# DK_STM32L151.net
KiCad netlist of a schematic drawn in Altium Designer
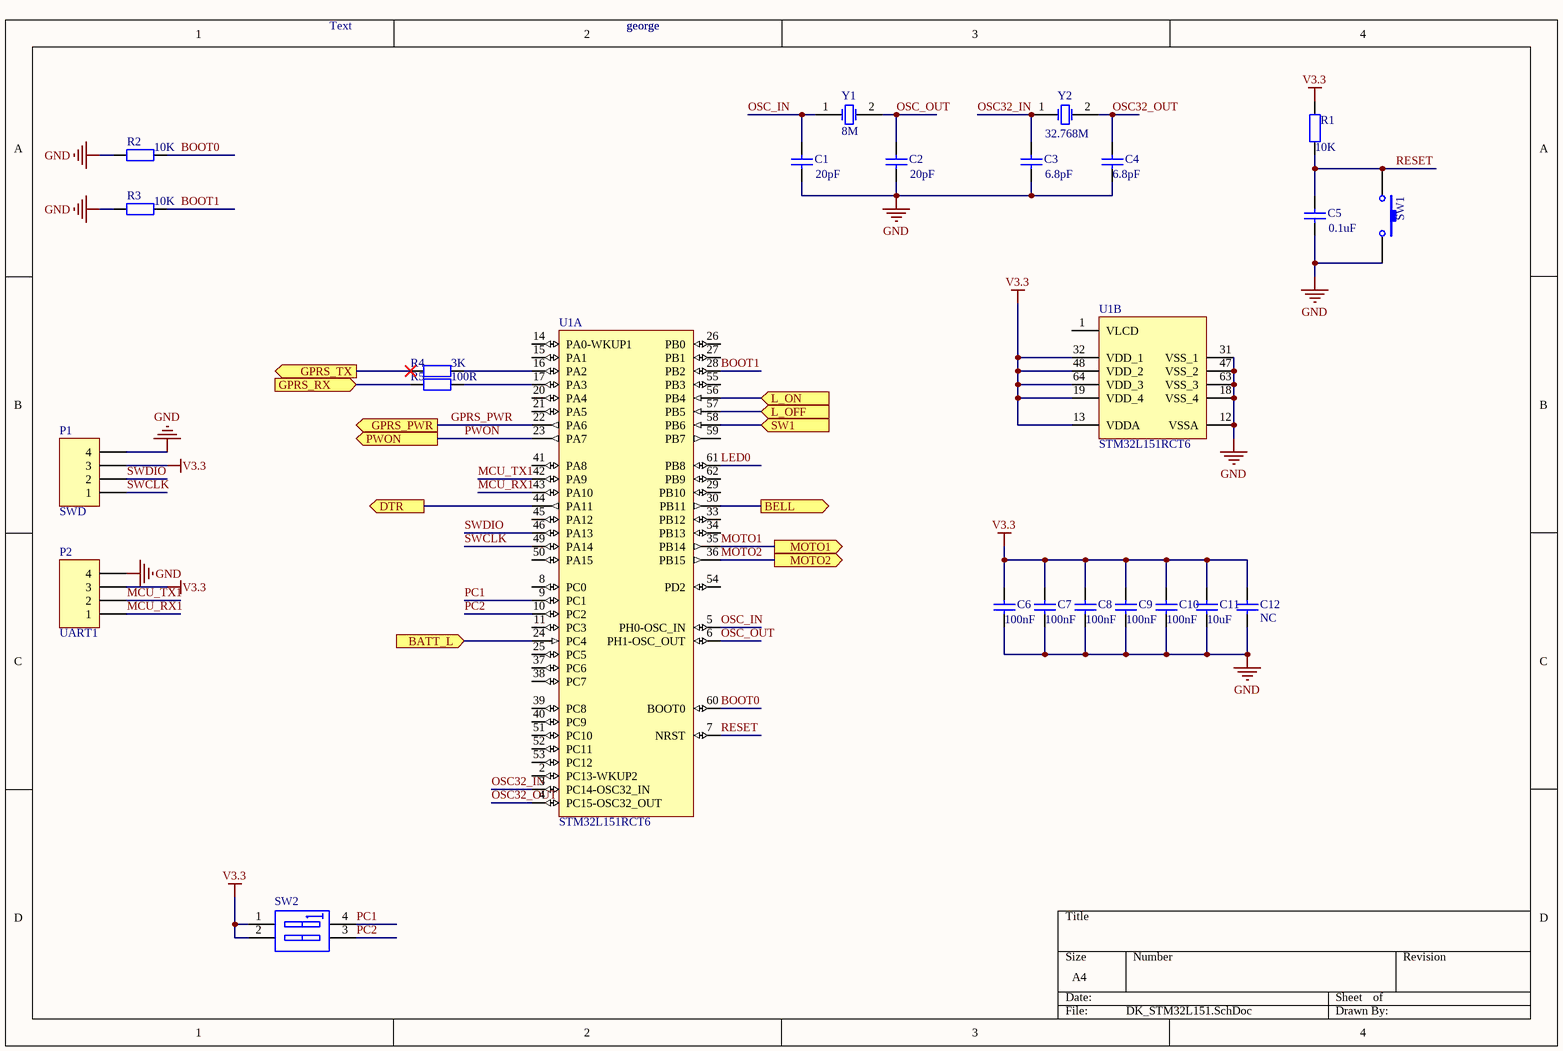
[diagram p0: DK_STM32L151.SchDoc]

(export (version "E")
  (design (tool "Eeschema 10.0.6"))
  (components
    (comp (ref "C1")
      (value "20pF")
      (footprint "0603")
      (description "Capacitor")
      (fields (field (name "Comment") "Cap") (field (name "PUBLISHER") "Altium Limited"))
      (libsource (lib "Miscellaneous Devices") (part "Cap"))
    )
    (comp (ref "C2")
      (value "20pF")
      (footprint "0603")
      (description "Capacitor")
      (fields (field (name "Comment") "Cap") (field (name "PUBLISHER") "Altium Limited"))
      (libsource (lib "Miscellaneous Devices") (part "Cap"))
    )
    (comp (ref "C3")
      (value "6.8pF")
      (footprint "0603")
      (description "Capacitor")
      (fields (field (name "Comment") "Cap") (field (name "PUBLISHER") "Altium Limited"))
      (libsource (lib "Miscellaneous Devices") (part "Cap"))
    )
    (comp (ref "C4")
      (value "6.8pF")
      (footprint "0603")
      (description "Capacitor")
      (fields (field (name "Comment") "Cap") (field (name "PUBLISHER") "Altium Limited"))
      (libsource (lib "Miscellaneous Devices") (part "Cap"))
    )
    (comp (ref "C5")
      (value "0.1uF")
      (footprint "0603")
      (description "Capacitor")
      (fields (field (name "Comment") "Cap") (field (name "PUBLISHER") "Altium Limited"))
      (libsource (lib "Miscellaneous Devices") (part "Cap"))
    )
    (comp (ref "C6")
      (value "100nF")
      (footprint "0603")
      (description "Capacitor")
      (fields (field (name "Comment") "Cap") (field (name "PUBLISHER") "Altium Limited"))
      (libsource (lib "Miscellaneous Devices") (part "Cap"))
    )
    (comp (ref "C7")
      (value "100nF")
      (footprint "0603")
      (description "Capacitor")
      (fields (field (name "Comment") "Cap") (field (name "PUBLISHER") "Altium Limited"))
      (libsource (lib "Miscellaneous Devices") (part "Cap"))
    )
    (comp (ref "C8")
      (value "100nF")
      (footprint "0603")
      (description "Capacitor")
      (fields (field (name "Comment") "Cap") (field (name "PUBLISHER") "Altium Limited"))
      (libsource (lib "Miscellaneous Devices") (part "Cap"))
    )
    (comp (ref "C9")
      (value "100nF")
      (footprint "0603")
      (description "Capacitor")
      (fields (field (name "Comment") "Cap") (field (name "PUBLISHER") "Altium Limited"))
      (libsource (lib "Miscellaneous Devices") (part "Cap"))
    )
    (comp (ref "C10")
      (value "100nF")
      (footprint "0603")
      (description "Capacitor")
      (fields (field (name "Comment") "Cap") (field (name "PUBLISHER") "Altium Limited"))
      (libsource (lib "Miscellaneous Devices") (part "Cap"))
    )
    (comp (ref "C11")
      (value "10uF")
      (footprint "0603")
      (description "Capacitor")
      (fields (field (name "Comment") "Cap") (field (name "PUBLISHER") "Altium Limited"))
      (libsource (lib "Miscellaneous Devices") (part "Cap"))
    )
    (comp (ref "C12")
      (value "NC")
      (footprint "0603")
      (description "Capacitor")
      (fields (field (name "PUBLISHER") "Altium Limited"))
      (libsource (lib "Miscellaneous Devices") (part "Cap"))
    )
    (comp (ref "P1")
      (value "SWD")
      (footprint "HDR1X4")
      (description "Header, 4-Pin")
      (fields (field (name "PUBLISHER") "Altium Limited"))
      (libsource (lib "Miscellaneous Connectors") (part "Header 4"))
    )
    (comp (ref "P2")
      (value "UART1")
      (footprint "HDR1X4")
      (description "Header, 4-Pin")
      (fields (field (name "PUBLISHER") "Altium Limited"))
      (libsource (lib "Miscellaneous Connectors") (part "Header 4"))
    )
    (comp (ref "R1")
      (value "10K")
      (footprint "0603")
      (description "Resistor")
      (fields (field (name "Comment") "Res2") (field (name "PUBLISHER") "Altium Limited"))
      (libsource (lib "") (part "Res2_1"))
    )
    (comp (ref "R2")
      (value "10K")
      (footprint "0603")
      (description "Resistor")
      (fields (field (name "Comment") "Res2") (field (name "PUBLISHER") "Altium Limited"))
      (libsource (lib "Miscellaneous Devices") (part "Res2"))
    )
    (comp (ref "R3")
      (value "10K")
      (footprint "0603")
      (description "Resistor")
      (fields (field (name "Comment") "Res2") (field (name "PUBLISHER") "Altium Limited"))
      (libsource (lib "Miscellaneous Devices") (part "Res2"))
    )
    (comp (ref "R4")
      (value "3K")
      (footprint "0603")
      (description "Resistor")
      (fields (field (name "Comment") "Res2") (field (name "PUBLISHER") "Altium Limited"))
      (libsource (lib "Miscellaneous Devices") (part "Res2"))
    )
    (comp (ref "R5")
      (value "100R")
      (footprint "0603")
      (description "Resistor")
      (fields (field (name "Comment") "Res2") (field (name "PUBLISHER") "Altium Limited"))
      (libsource (lib "Miscellaneous Devices") (part "Res2"))
    )
    (comp (ref "SW1")
      (value "SW-PB")
      (footprint "3*6*4.3")
      (description "Switch")
      (fields (field (name "PUBLISHER") "Altium Limited"))
      (libsource (lib "Miscellaneous Devices") (part "SW-PB"))
    )
    (comp (ref "SW2")
      (value "SW DIP-2")
      (footprint "SW-2*4")
      (description "DIP Switch, 2 Position, SPST")
      (fields (field (name "PUBLISHER") "Altium Limited"))
      (libsource (lib "Miscellaneous Devices") (part "SW DIP-2"))
    )
    (comp (ref "U1")
      (value "STM32L151RCT6")
      (footprint "LQFP64")
      (fields (field (name "MANUFACTURER") "STMicroelectronics"))
      (libsource (lib "STMicroelectronics STM32 L1") (part "STM32L151RCT6"))
    )
    (comp (ref "Y1")
      (value "8M")
      (footprint "SMT-OSC")
      (description "Crystal Oscillator")
      (fields (field (name "PUBLISHER") "Altium Limited"))
      (libsource (lib "Miscellaneous Devices") (part "XTAL"))
    )
    (comp (ref "Y2")
      (value "32.768M")
      (footprint "XTAL32.786")
      (description "Crystal Oscillator")
      (fields (field (name "PUBLISHER") "Altium Limited"))
      (libsource (lib "Miscellaneous Devices") (part "XTAL"))
    )
  )
  (nets
    (net (code "1") (name "/BATT_L") (class "Default")
      (node (ref "U1") (pin "24") (pinfunction "PC4_24") (pintype "input"))
    )
    (net (code "2") (name "/BELL") (class "Default")
      (node (ref "U1") (pin "30") (pinfunction "PB11_30") (pintype "output"))
    )
    (net (code "3") (name "/BOOT0") (class "Default")
      (node (ref "R2") (pin "2") (pinfunction "2_2") (pintype "passive"))
      (node (ref "U1") (pin "60") (pinfunction "BOOT0_60") (pintype "bidirectional"))
    )
    (net (code "4") (name "/BOOT1") (class "Default")
      (node (ref "R3") (pin "2") (pinfunction "2_2") (pintype "passive"))
      (node (ref "U1") (pin "28") (pinfunction "PB2_28") (pintype "bidirectional"))
    )
    (net (code "5") (name "/DTR") (class "Default")
      (node (ref "U1") (pin "44") (pinfunction "PA11_44") (pintype "output"))
    )
    (net (code "6") (name "/GPRS_PWR") (class "Default")
      (node (ref "U1") (pin "22") (pinfunction "PA6_22") (pintype "output"))
    )
    (net (code "7") (name "/GPRS_RX") (class "Default")
      (node (ref "R5") (pin "1") (pinfunction "1_1") (pintype "passive"))
    )
    (net (code "8") (name "/GPRS_TX") (class "Default")
      (node (ref "R4") (pin "1") (pinfunction "1_1") (pintype "passive+no_connect"))
    )
    (net (code "9") (name "/LED0") (class "Default")
      (node (ref "U1") (pin "61") (pinfunction "PB8_61") (pintype "bidirectional"))
    )
    (net (code "10") (name "/L_OFF") (class "Default")
      (node (ref "U1") (pin "57") (pinfunction "PB5_57") (pintype "input"))
    )
    (net (code "11") (name "/L_ON") (class "Default")
      (node (ref "U1") (pin "56") (pinfunction "PB4_56") (pintype "input"))
    )
    (net (code "12") (name "/MCU_RX1") (class "Default")
      (node (ref "P2") (pin "1") (pinfunction "1_1") (pintype "passive"))
      (node (ref "U1") (pin "43") (pinfunction "PA10_43") (pintype "bidirectional"))
    )
    (net (code "13") (name "/MCU_TX1") (class "Default")
      (node (ref "P2") (pin "2") (pinfunction "2_2") (pintype "passive"))
      (node (ref "U1") (pin "42") (pinfunction "PA9_42") (pintype "bidirectional"))
    )
    (net (code "14") (name "/MOTO1") (class "Default")
      (node (ref "U1") (pin "35") (pinfunction "PB14_35") (pintype "output"))
    )
    (net (code "15") (name "/MOTO2") (class "Default")
      (node (ref "U1") (pin "36") (pinfunction "PB15_36") (pintype "output"))
    )
    (net (code "16") (name "/OSC32_IN") (class "Default")
      (node (ref "C3") (pin "2") (pinfunction "2_2") (pintype "passive"))
      (node (ref "U1") (pin "3") (pinfunction "PC14-OSC32_IN_3") (pintype "bidirectional"))
      (node (ref "Y2") (pin "1") (pinfunction "OSC1_1") (pintype "passive"))
    )
    (net (code "17") (name "/OSC32_OUT") (class "Default")
      (node (ref "C4") (pin "2") (pinfunction "2_2") (pintype "passive"))
      (node (ref "U1") (pin "4") (pinfunction "PC15-OSC32_OUT_4") (pintype "bidirectional"))
      (node (ref "Y2") (pin "2") (pinfunction "OSC2_2") (pintype "passive"))
    )
    (net (code "18") (name "/OSC_IN") (class "Default")
      (node (ref "C1") (pin "2") (pinfunction "2_2") (pintype "passive"))
      (node (ref "U1") (pin "5") (pinfunction "PH0-OSC_IN_5") (pintype "bidirectional"))
      (node (ref "Y1") (pin "1") (pinfunction "OSC1_1") (pintype "passive"))
    )
    (net (code "19") (name "/OSC_OUT") (class "Default")
      (node (ref "C2") (pin "2") (pinfunction "2_2") (pintype "passive"))
      (node (ref "U1") (pin "6") (pinfunction "PH1-OSC_OUT_6") (pintype "bidirectional"))
      (node (ref "Y1") (pin "2") (pinfunction "OSC2_2") (pintype "passive"))
    )
    (net (code "20") (name "/PC1") (class "Default")
      (node (ref "SW2") (pin "4") (pinfunction "B1_4") (pintype "passive"))
      (node (ref "U1") (pin "9") (pinfunction "PC1_9") (pintype "bidirectional"))
    )
    (net (code "21") (name "/PC2") (class "Default")
      (node (ref "SW2") (pin "3") (pinfunction "B2_3") (pintype "passive"))
      (node (ref "U1") (pin "10") (pinfunction "PC2_10") (pintype "bidirectional"))
    )
    (net (code "22") (name "/PWON") (class "Default")
      (node (ref "U1") (pin "23") (pinfunction "PA7_23") (pintype "output"))
    )
    (net (code "23") (name "/RESET") (class "Default")
      (node (ref "C5") (pin "1") (pinfunction "1_1") (pintype "passive"))
      (node (ref "R1") (pin "2") (pinfunction "2_2") (pintype "passive"))
      (node (ref "SW1") (pin "1") (pinfunction "1_1") (pintype "passive"))
      (node (ref "U1") (pin "7") (pinfunction "NRST_7") (pintype "bidirectional"))
    )
    (net (code "24") (name "/SW1") (class "Default")
      (node (ref "U1") (pin "58") (pinfunction "PB6_58") (pintype "input"))
    )
    (net (code "25") (name "/SWCLK") (class "Default")
      (node (ref "P1") (pin "1") (pinfunction "1_1") (pintype "passive"))
      (node (ref "U1") (pin "49") (pinfunction "PA14_49") (pintype "bidirectional"))
    )
    (net (code "26") (name "/SWDIO") (class "Default")
      (node (ref "P1") (pin "2") (pinfunction "2_2") (pintype "passive"))
      (node (ref "U1") (pin "46") (pinfunction "PA13_46") (pintype "bidirectional"))
    )
    (net (code "27") (name "GND") (class "Default")
      (node (ref "C1") (pin "1") (pinfunction "1_1") (pintype "passive"))
      (node (ref "C10") (pin "1") (pinfunction "1_1") (pintype "passive"))
      (node (ref "C11") (pin "1") (pinfunction "1_1") (pintype "passive"))
      (node (ref "C12") (pin "1") (pinfunction "1_1") (pintype "passive"))
      (node (ref "C2") (pin "1") (pinfunction "1_1") (pintype "passive"))
      (node (ref "C3") (pin "1") (pinfunction "1_1") (pintype "passive"))
      (node (ref "C4") (pin "1") (pinfunction "1_1") (pintype "passive"))
      (node (ref "C5") (pin "2") (pinfunction "2_2") (pintype "passive"))
      (node (ref "C6") (pin "1") (pinfunction "1_1") (pintype "passive"))
      (node (ref "C7") (pin "1") (pinfunction "1_1") (pintype "passive"))
      (node (ref "C8") (pin "1") (pinfunction "1_1") (pintype "passive"))
      (node (ref "C9") (pin "1") (pinfunction "1_1") (pintype "passive"))
      (node (ref "P1") (pin "4") (pinfunction "4_4") (pintype "passive"))
      (node (ref "P2") (pin "4") (pinfunction "4_4") (pintype "passive"))
      (node (ref "R2") (pin "1") (pinfunction "1_1") (pintype "passive"))
      (node (ref "R3") (pin "1") (pinfunction "1_1") (pintype "passive"))
      (node (ref "SW1") (pin "2") (pinfunction "2_2") (pintype "passive"))
      (node (ref "U1") (pin "12") (pinfunction "VSSA_12") (pintype "power_in"))
      (node (ref "U1") (pin "18") (pinfunction "VSS_4_18") (pintype "power_in"))
      (node (ref "U1") (pin "31") (pinfunction "VSS_1_31") (pintype "power_in"))
      (node (ref "U1") (pin "47") (pinfunction "VSS_2_47") (pintype "power_in"))
      (node (ref "U1") (pin "63") (pinfunction "VSS_3_63") (pintype "power_in"))
    )
    (net (code "28") (name "Net-(U1A-PA2)") (class "Default")
      (node (ref "R4") (pin "2") (pinfunction "2_2") (pintype "passive"))
      (node (ref "U1") (pin "16") (pinfunction "PA2_16") (pintype "bidirectional"))
    )
    (net (code "29") (name "Net-(U1A-PA3)") (class "Default")
      (node (ref "R5") (pin "2") (pinfunction "2_2") (pintype "passive"))
      (node (ref "U1") (pin "17") (pinfunction "PA3_17") (pintype "bidirectional"))
    )
    (net (code "30") (name "V3.3") (class "Default")
      (node (ref "C10") (pin "2") (pinfunction "2_2") (pintype "passive"))
      (node (ref "C11") (pin "2") (pinfunction "2_2") (pintype "passive"))
      (node (ref "C12") (pin "2") (pinfunction "2_2") (pintype "passive"))
      (node (ref "C6") (pin "2") (pinfunction "2_2") (pintype "passive"))
      (node (ref "C7") (pin "2") (pinfunction "2_2") (pintype "passive"))
      (node (ref "C8") (pin "2") (pinfunction "2_2") (pintype "passive"))
      (node (ref "C9") (pin "2") (pinfunction "2_2") (pintype "passive"))
      (node (ref "P1") (pin "3") (pinfunction "3_3") (pintype "passive"))
      (node (ref "P2") (pin "3") (pinfunction "3_3") (pintype "passive"))
      (node (ref "R1") (pin "1") (pinfunction "1_1") (pintype "passive"))
      (node (ref "SW2") (pin "1") (pinfunction "A1_1") (pintype "passive"))
      (node (ref "SW2") (pin "2") (pinfunction "A2_2") (pintype "passive"))
      (node (ref "U1") (pin "13") (pinfunction "VDDA_13") (pintype "power_in"))
      (node (ref "U1") (pin "19") (pinfunction "VDD_4_19") (pintype "power_in"))
      (node (ref "U1") (pin "32") (pinfunction "VDD_1_32") (pintype "power_in"))
      (node (ref "U1") (pin "48") (pinfunction "VDD_2_48") (pintype "power_in"))
      (node (ref "U1") (pin "64") (pinfunction "VDD_3_64") (pintype "power_in"))
    )
    (net (code "31") (name "unconnected-(U1A-PA0-WKUP1-Pad14)") (class "Default")
      (node (ref "U1") (pin "14") (pinfunction "PA0-WKUP1_14") (pintype "bidirectional"))
    )
    (net (code "32") (name "unconnected-(U1A-PA1-Pad15)") (class "Default")
      (node (ref "U1") (pin "15") (pinfunction "PA1_15") (pintype "bidirectional"))
    )
    (net (code "33") (name "unconnected-(U1A-PA4-Pad20)") (class "Default")
      (node (ref "U1") (pin "20") (pinfunction "PA4_20") (pintype "bidirectional"))
    )
    (net (code "34") (name "unconnected-(U1A-PA5-Pad21)") (class "Default")
      (node (ref "U1") (pin "21") (pinfunction "PA5_21") (pintype "bidirectional"))
    )
    (net (code "35") (name "unconnected-(U1A-PA8-Pad41)") (class "Default")
      (node (ref "U1") (pin "41") (pinfunction "PA8_41") (pintype "bidirectional"))
    )
    (net (code "36") (name "unconnected-(U1A-PA12-Pad45)") (class "Default")
      (node (ref "U1") (pin "45") (pinfunction "PA12_45") (pintype "bidirectional"))
    )
    (net (code "37") (name "unconnected-(U1A-PA15-Pad50)") (class "Default")
      (node (ref "U1") (pin "50") (pinfunction "PA15_50") (pintype "bidirectional"))
    )
    (net (code "38") (name "unconnected-(U1A-PB0-Pad26)") (class "Default")
      (node (ref "U1") (pin "26") (pinfunction "PB0_26") (pintype "bidirectional"))
    )
    (net (code "39") (name "unconnected-(U1A-PB1-Pad27)") (class "Default")
      (node (ref "U1") (pin "27") (pinfunction "PB1_27") (pintype "bidirectional"))
    )
    (net (code "40") (name "unconnected-(U1A-PB3-Pad55)") (class "Default")
      (node (ref "U1") (pin "55") (pinfunction "PB3_55") (pintype "bidirectional"))
    )
    (net (code "41") (name "unconnected-(U1A-PB7-Pad59)") (class "Default")
      (node (ref "U1") (pin "59") (pinfunction "PB7_59") (pintype "output"))
    )
    (net (code "42") (name "unconnected-(U1A-PB9-Pad62)") (class "Default")
      (node (ref "U1") (pin "62") (pinfunction "PB9_62") (pintype "bidirectional"))
    )
    (net (code "43") (name "unconnected-(U1A-PB10-Pad29)") (class "Default")
      (node (ref "U1") (pin "29") (pinfunction "PB10_29") (pintype "bidirectional"))
    )
    (net (code "44") (name "unconnected-(U1A-PB12-Pad33)") (class "Default")
      (node (ref "U1") (pin "33") (pinfunction "PB12_33") (pintype "bidirectional"))
    )
    (net (code "45") (name "unconnected-(U1A-PB13-Pad34)") (class "Default")
      (node (ref "U1") (pin "34") (pinfunction "PB13_34") (pintype "bidirectional"))
    )
    (net (code "46") (name "unconnected-(U1A-PC0-Pad8)") (class "Default")
      (node (ref "U1") (pin "8") (pinfunction "PC0_8") (pintype "bidirectional"))
    )
    (net (code "47") (name "unconnected-(U1A-PC3-Pad11)") (class "Default")
      (node (ref "U1") (pin "11") (pinfunction "PC3_11") (pintype "bidirectional"))
    )
    (net (code "48") (name "unconnected-(U1A-PC5-Pad25)") (class "Default")
      (node (ref "U1") (pin "25") (pinfunction "PC5_25") (pintype "bidirectional"))
    )
    (net (code "49") (name "unconnected-(U1A-PC6-Pad37)") (class "Default")
      (node (ref "U1") (pin "37") (pinfunction "PC6_37") (pintype "bidirectional"))
    )
    (net (code "50") (name "unconnected-(U1A-PC7-Pad38)") (class "Default")
      (node (ref "U1") (pin "38") (pinfunction "PC7_38") (pintype "bidirectional"))
    )
    (net (code "51") (name "unconnected-(U1A-PC8-Pad39)") (class "Default")
      (node (ref "U1") (pin "39") (pinfunction "PC8_39") (pintype "bidirectional"))
    )
    (net (code "52") (name "unconnected-(U1A-PC9-Pad40)") (class "Default")
      (node (ref "U1") (pin "40") (pinfunction "PC9_40") (pintype "bidirectional"))
    )
    (net (code "53") (name "unconnected-(U1A-PC10-Pad51)") (class "Default")
      (node (ref "U1") (pin "51") (pinfunction "PC10_51") (pintype "bidirectional"))
    )
    (net (code "54") (name "unconnected-(U1A-PC11-Pad52)") (class "Default")
      (node (ref "U1") (pin "52") (pinfunction "PC11_52") (pintype "bidirectional"))
    )
    (net (code "55") (name "unconnected-(U1A-PC12-Pad53)") (class "Default")
      (node (ref "U1") (pin "53") (pinfunction "PC12_53") (pintype "bidirectional"))
    )
    (net (code "56") (name "unconnected-(U1A-PC13-WKUP2-Pad2)") (class "Default")
      (node (ref "U1") (pin "2") (pinfunction "PC13-WKUP2_2") (pintype "bidirectional"))
    )
    (net (code "57") (name "unconnected-(U1A-PD2-Pad54)") (class "Default")
      (node (ref "U1") (pin "54") (pinfunction "PD2_54") (pintype "bidirectional"))
    )
    (net (code "58") (name "unconnected-(U1B-VLCD-Pad1)") (class "Default")
      (node (ref "U1") (pin "1") (pinfunction "VLCD_1") (pintype "power_in"))
    )
  )
)
